# MAIN_AV_Final.net
KiCad netlist of a schematic drawn in EAGLE
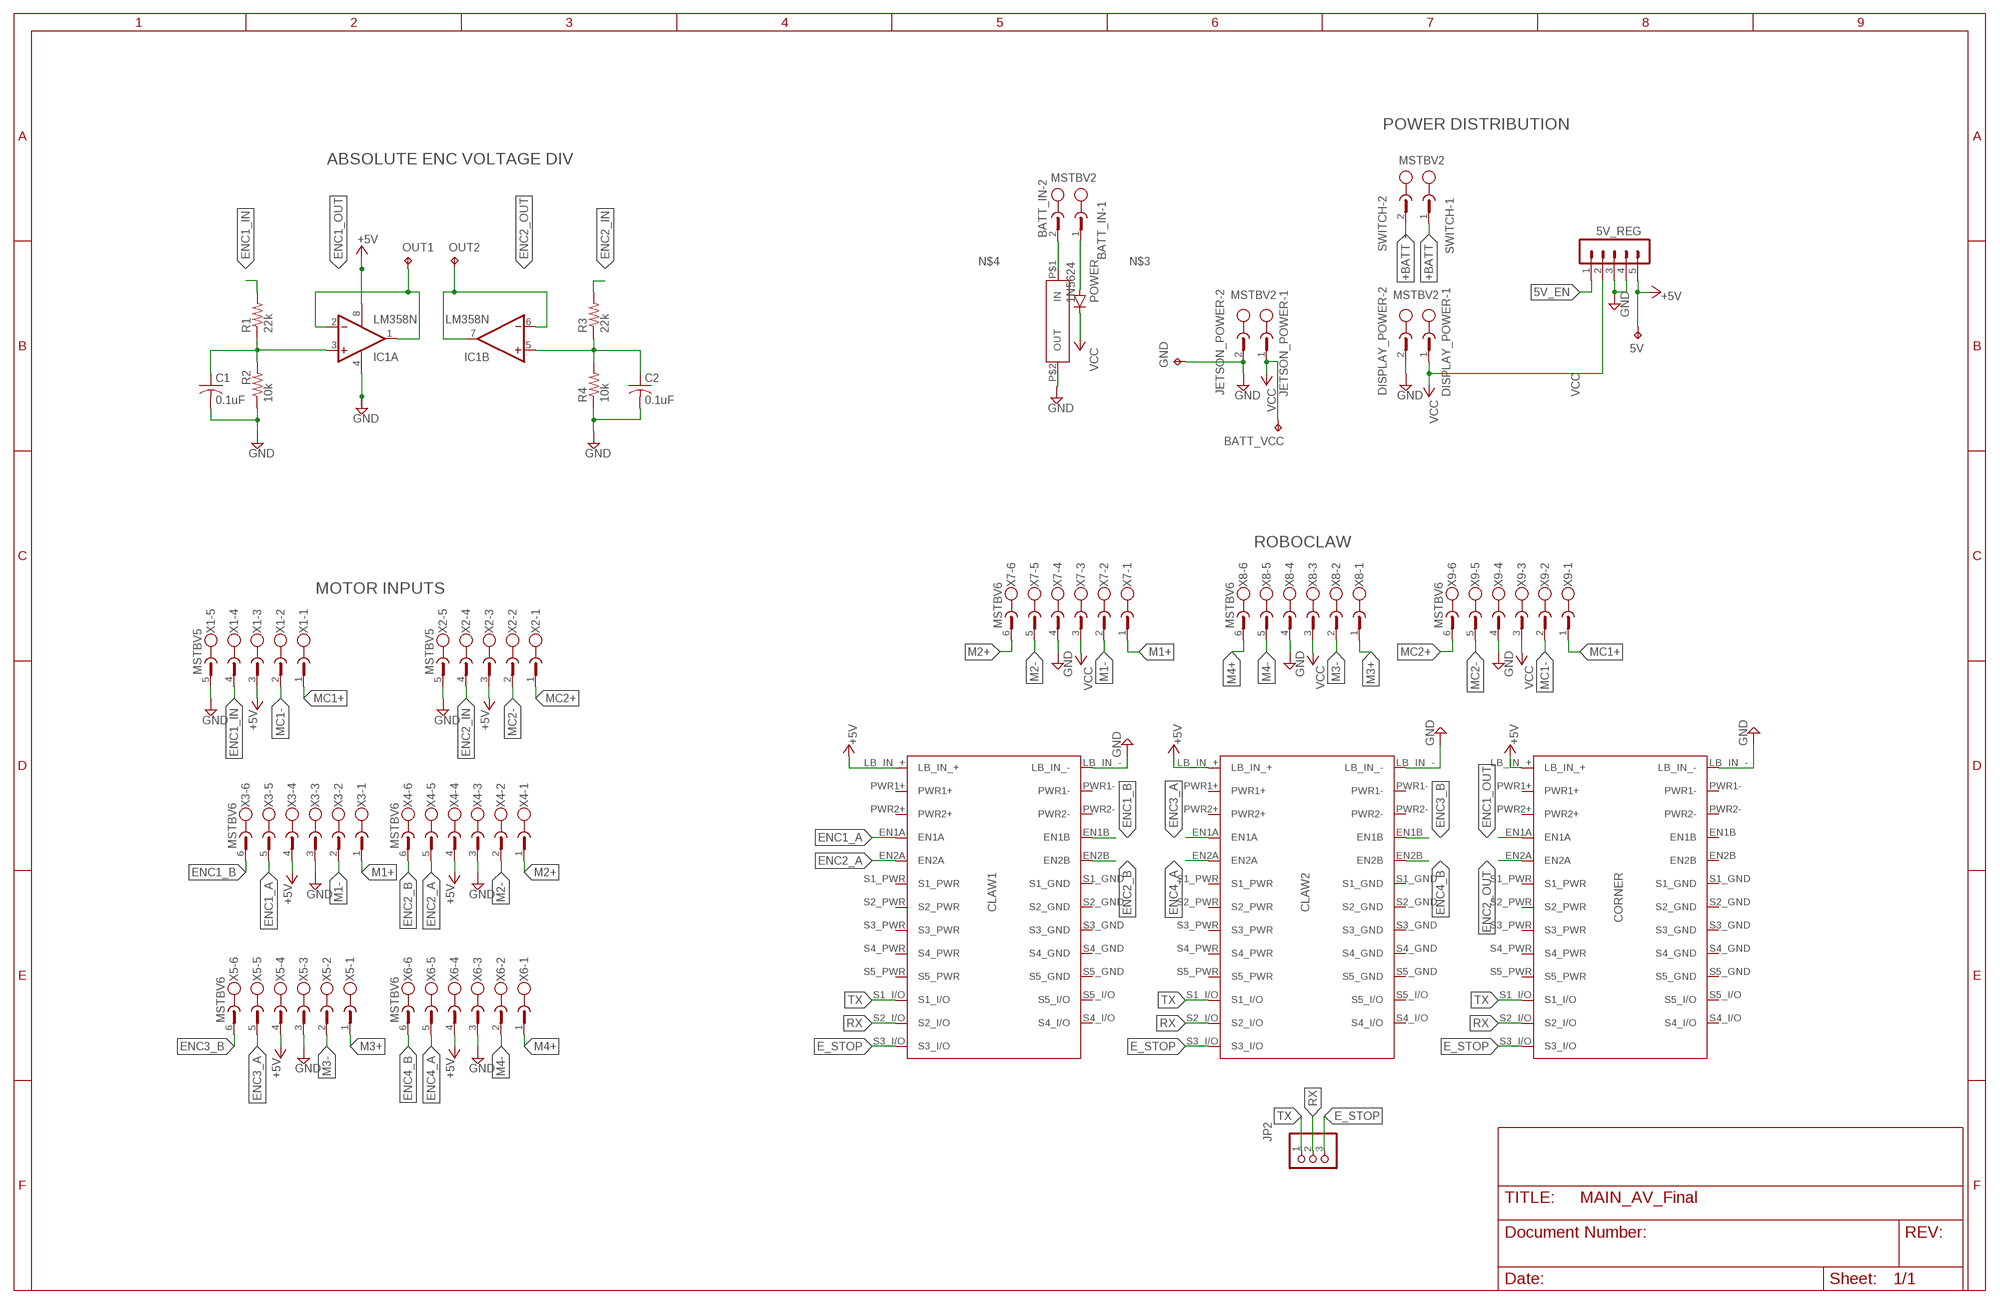
[diagram p0: schematic, sheet 1]

(export (version "E")
  (design (tool "Eeschema 10.0.6"))
  (components
    (comp (ref "5V")
      (value "TPTP10SQ")
      (footprint "eagle-import:TP10SQ")
      (libsource (lib "eagle-import") (part "TPTP10SQ"))
    )
    (comp (ref "5V_REG")
      (value "MA05-1")
      (footprint "eagle-import:MA05-1")
      (libsource (lib "eagle-import") (part "MA05-1"))
    )
    (comp (ref "BATT_IN")
      (value "MSTBV2")
      (footprint "eagle-import:MSTBV2")
      (fields (field (name "MPN") "MSTBV 2,5/2-GF-5.08"))
      (libsource (lib "eagle-import") (part "MSTBV2"))
    )
    (comp (ref "BATT_VCC")
      (value "TPTP10SQ")
      (footprint "eagle-import:TP10SQ")
      (libsource (lib "eagle-import") (part "TPTP10SQ"))
    )
    (comp (ref "C1")
      (value "0.1uF")
      (footprint "eagle-import:C050-024X044")
      (libsource (lib "eagle-import") (part "C-US050-024X044"))
    )
    (comp (ref "C2")
      (value "0.1uF")
      (footprint "eagle-import:C050-024X044")
      (libsource (lib "eagle-import") (part "C-US050-024X044"))
    )
    (comp (ref "CLAW1")
      (value "ROBOCLAW2X7A")
      (footprint "eagle-import:ROBOCLAW")
      (libsource (lib "eagle-import") (part "ROBOCLAW2X7A"))
    )
    (comp (ref "CLAW2")
      (value "ROBOCLAW2X7A")
      (footprint "eagle-import:ROBOCLAW")
      (libsource (lib "eagle-import") (part "ROBOCLAW2X7A"))
    )
    (comp (ref "CORNER")
      (value "ROBOCLAW2X7A")
      (footprint "eagle-import:ROBOCLAW")
      (libsource (lib "eagle-import") (part "ROBOCLAW2X7A"))
    )
    (comp (ref "DISPLAY_POWER")
      (value "MSTBV2")
      (footprint "eagle-import:MSTBV2")
      (fields (field (name "MPN") "MSTBV 2,5/2-GF-5.08"))
      (libsource (lib "eagle-import") (part "MSTBV2"))
    )
    (comp (ref "GND")
      (value "TPTP10SQ")
      (footprint "eagle-import:TP10SQ")
      (libsource (lib "eagle-import") (part "TPTP10SQ"))
    )
    (comp (ref "IC1")
      (value "LM358N")
      (footprint "eagle-import:DIL08")
      (libsource (lib "eagle-import") (part "LM358N"))
    )
    (comp (ref "JETSON_POWER")
      (value "MSTBV2")
      (footprint "eagle-import:MSTBV2")
      (fields (field (name "MPN") "MSTBV 2,5/2-GF-5.08"))
      (libsource (lib "eagle-import") (part "MSTBV2"))
    )
    (comp (ref "JP2")
      (value "PINHD-1X3")
      (footprint "eagle-import:1X03")
      (libsource (lib "eagle-import") (part "PINHD-1X3"))
    )
    (comp (ref "OUT1")
      (value "TPTP10SQ")
      (footprint "eagle-import:TP10SQ")
      (libsource (lib "eagle-import") (part "TPTP10SQ"))
    )
    (comp (ref "OUT2")
      (value "TPTP10SQ")
      (footprint "eagle-import:TP10SQ")
      (libsource (lib "eagle-import") (part "TPTP10SQ"))
    )
    (comp (ref "POWER")
      (value "1N5624")
      (footprint "eagle-import:DO201-15")
      (libsource (lib "eagle-import") (part "1N5624"))
    )
    (comp (ref "R1")
      (value "22k")
      (footprint "eagle-import:0204_7")
      (libsource (lib "eagle-import") (part "R-US_0204/7"))
    )
    (comp (ref "R2")
      (value "10k")
      (footprint "eagle-import:0204_7")
      (libsource (lib "eagle-import") (part "R-US_0204/7"))
    )
    (comp (ref "R3")
      (value "22k")
      (footprint "eagle-import:0204_7")
      (libsource (lib "eagle-import") (part "R-US_0204/7"))
    )
    (comp (ref "R4")
      (value "10k")
      (footprint "eagle-import:0204_7")
      (libsource (lib "eagle-import") (part "R-US_0204/7"))
    )
    (comp (ref "SWITCH")
      (value "MSTBV2")
      (footprint "eagle-import:MSTBV2")
      (fields (field (name "MPN") "MSTBV 2,5/2-GF-5.08"))
      (libsource (lib "eagle-import") (part "MSTBV2"))
    )
    (comp (ref "U$1")
      (value "FUSEHOLDER")
      (footprint "eagle-import:FUSEHOLDER")
      (libsource (lib "eagle-import") (part "FUSEHOLDER"))
    )
    (comp (ref "X1")
      (value "MSTBV5")
      (footprint "eagle-import:MSTBV5")
      (fields (field (name "MPN") "MSTBV 2,5/5-GF-5.08"))
      (libsource (lib "eagle-import") (part "MSTBV5"))
    )
    (comp (ref "X2")
      (value "MSTBV5")
      (footprint "eagle-import:MSTBV5")
      (fields (field (name "MPN") "MSTBV 2,5/5-GF-5.08"))
      (libsource (lib "eagle-import") (part "MSTBV5"))
    )
    (comp (ref "X3")
      (value "MSTBV6")
      (footprint "eagle-import:MSTBV6")
      (fields (field (name "MPN") "MSTBV 2,5/6-GF-5.08"))
      (libsource (lib "eagle-import") (part "MSTBV6"))
    )
    (comp (ref "X4")
      (value "MSTBV6")
      (footprint "eagle-import:MSTBV6")
      (fields (field (name "MPN") "MSTBV 2,5/6-GF-5.08"))
      (libsource (lib "eagle-import") (part "MSTBV6"))
    )
    (comp (ref "X5")
      (value "MSTBV6")
      (footprint "eagle-import:MSTBV6")
      (fields (field (name "MPN") "MSTBV 2,5/6-GF-5.08"))
      (libsource (lib "eagle-import") (part "MSTBV6"))
    )
    (comp (ref "X6")
      (value "MSTBV6")
      (footprint "eagle-import:MSTBV6")
      (fields (field (name "MPN") "MSTBV 2,5/6-GF-5.08"))
      (libsource (lib "eagle-import") (part "MSTBV6"))
    )
    (comp (ref "X7")
      (value "MSTBV6")
      (footprint "eagle-import:MSTBV6")
      (fields (field (name "MPN") "MSTBV 2,5/6-GF-5.08"))
      (libsource (lib "eagle-import") (part "MSTBV6"))
    )
    (comp (ref "X8")
      (value "MSTBV6")
      (footprint "eagle-import:MSTBV6")
      (fields (field (name "MPN") "MSTBV 2,5/6-GF-5.08"))
      (libsource (lib "eagle-import") (part "MSTBV6"))
    )
    (comp (ref "X9")
      (value "MSTBV6")
      (footprint "eagle-import:MSTBV6")
      (fields (field (name "MPN") "MSTBV 2,5/6-GF-5.08"))
      (libsource (lib "eagle-import") (part "MSTBV6"))
    )
  )
  (nets
    (net (code "1") (name "+5V") (class "Default")
      (node (ref "5V") (pin "TP") (pinfunction "TP_TP") (pintype "input"))
      (node (ref "5V_REG") (pin "5") (pinfunction "5_5") (pintype "passive"))
      (node (ref "CLAW1") (pin "LB_IN_+") (pinfunction "LB_IN_+_LB_IN_+") (pintype "bidirectional"))
      (node (ref "CLAW2") (pin "LB_IN_+") (pinfunction "LB_IN_+_LB_IN_+") (pintype "bidirectional"))
      (node (ref "CORNER") (pin "LB_IN_+") (pinfunction "LB_IN_+_LB_IN_+") (pintype "bidirectional"))
      (node (ref "IC1") (pin "8") (pinfunction "V+_8") (pintype "power_in"))
      (node (ref "X1") (pin "3") (pinfunction "1_3") (pintype "passive"))
      (node (ref "X2") (pin "3") (pinfunction "1_3") (pintype "passive"))
      (node (ref "X3") (pin "4") (pinfunction "1_4") (pintype "passive"))
      (node (ref "X4") (pin "4") (pinfunction "1_4") (pintype "passive"))
      (node (ref "X5") (pin "4") (pinfunction "1_4") (pintype "passive"))
      (node (ref "X6") (pin "4") (pinfunction "1_4") (pintype "passive"))
    )
    (net (code "2") (name "+BATT") (class "Default")
      (node (ref "SWITCH") (pin "1") (pinfunction "1_1") (pintype "passive"))
      (node (ref "SWITCH") (pin "2") (pinfunction "1_2") (pintype "passive"))
    )
    (net (code "3") (name "/N$3") (class "Default")
      (node (ref "BATT_IN") (pin "1") (pinfunction "1_1") (pintype "passive"))
      (node (ref "POWER") (pin "A") (pinfunction "A_A") (pintype "passive"))
    )
    (net (code "4") (name "/N$4") (class "Default")
      (node (ref "BATT_IN") (pin "2") (pinfunction "1_2") (pintype "passive"))
      (node (ref "U$1") (pin "P$1") (pinfunction "IN_P$1") (pintype "bidirectional"))
    )
    (net (code "5") (name "5V_EN") (class "Default")
      (node (ref "5V_REG") (pin "1") (pinfunction "1_1") (pintype "passive"))
    )
    (net (code "6") (name "ENC1_A") (class "Default")
      (node (ref "CLAW1") (pin "EN1A") (pinfunction "EN1A_EN1A") (pintype "bidirectional"))
      (node (ref "X3") (pin "5") (pinfunction "1_5") (pintype "passive"))
    )
    (net (code "7") (name "ENC1_B") (class "Default")
      (node (ref "CLAW1") (pin "EN1B") (pinfunction "EN1B_EN1B") (pintype "bidirectional"))
      (node (ref "X3") (pin "6") (pinfunction "1_6") (pintype "passive"))
    )
    (net (code "8") (name "ENC1_IN") (class "Default")
      (node (ref "R1") (pin "2") (pinfunction "2_2") (pintype "passive"))
      (node (ref "X1") (pin "4") (pinfunction "1_4") (pintype "passive"))
    )
    (net (code "9") (name "ENC1_OUT") (class "Default")
      (node (ref "CORNER") (pin "EN1A") (pinfunction "EN1A_EN1A") (pintype "bidirectional"))
      (node (ref "IC1") (pin "1") (pinfunction "OUT_1") (pintype "output"))
      (node (ref "IC1") (pin "2") (pinfunction "-IN_2") (pintype "input"))
      (node (ref "OUT1") (pin "TP") (pinfunction "TP_TP") (pintype "input"))
    )
    (net (code "10") (name "ENC2_A") (class "Default")
      (node (ref "CLAW1") (pin "EN2A") (pinfunction "EN2A_EN2A") (pintype "bidirectional"))
      (node (ref "X4") (pin "5") (pinfunction "1_5") (pintype "passive"))
    )
    (net (code "11") (name "ENC2_B") (class "Default")
      (node (ref "CLAW1") (pin "EN2B") (pinfunction "EN2B_EN2B") (pintype "bidirectional"))
      (node (ref "X4") (pin "6") (pinfunction "1_6") (pintype "passive"))
    )
    (net (code "12") (name "ENC2_IN") (class "Default")
      (node (ref "R3") (pin "2") (pinfunction "2_2") (pintype "passive"))
      (node (ref "X2") (pin "4") (pinfunction "1_4") (pintype "passive"))
    )
    (net (code "13") (name "ENC2_OUT") (class "Default")
      (node (ref "CORNER") (pin "EN2A") (pinfunction "EN2A_EN2A") (pintype "bidirectional"))
      (node (ref "IC1") (pin "6") (pinfunction "-IN_6") (pintype "input"))
      (node (ref "IC1") (pin "7") (pinfunction "OUT_7") (pintype "output"))
      (node (ref "OUT2") (pin "TP") (pinfunction "TP_TP") (pintype "input"))
    )
    (net (code "14") (name "ENC3_A") (class "Default")
      (node (ref "CLAW2") (pin "EN1A") (pinfunction "EN1A_EN1A") (pintype "bidirectional"))
      (node (ref "X5") (pin "5") (pinfunction "1_5") (pintype "passive"))
    )
    (net (code "15") (name "ENC3_B") (class "Default")
      (node (ref "CLAW2") (pin "EN1B") (pinfunction "EN1B_EN1B") (pintype "bidirectional"))
      (node (ref "X5") (pin "6") (pinfunction "1_6") (pintype "passive"))
    )
    (net (code "16") (name "ENC4_A") (class "Default")
      (node (ref "CLAW2") (pin "EN2A") (pinfunction "EN2A_EN2A") (pintype "bidirectional"))
      (node (ref "X6") (pin "5") (pinfunction "1_5") (pintype "passive"))
    )
    (net (code "17") (name "ENC4_B") (class "Default")
      (node (ref "CLAW2") (pin "EN2B") (pinfunction "EN2B_EN2B") (pintype "bidirectional"))
      (node (ref "X6") (pin "6") (pinfunction "1_6") (pintype "passive"))
    )
    (net (code "18") (name "E_STOP") (class "Default")
      (node (ref "CLAW1") (pin "S3_I/O") (pinfunction "S3_I/O_S3_I/O") (pintype "bidirectional"))
      (node (ref "CLAW2") (pin "S3_I/O") (pinfunction "S3_I/O_S3_I/O") (pintype "bidirectional"))
      (node (ref "CORNER") (pin "S3_I/O") (pinfunction "S3_I/O_S3_I/O") (pintype "bidirectional"))
      (node (ref "JP2") (pin "3") (pinfunction "3_3") (pintype "passive"))
    )
    (net (code "19") (name "GND") (class "Default")
      (node (ref "5V_REG") (pin "3") (pinfunction "3_3") (pintype "passive"))
      (node (ref "5V_REG") (pin "4") (pinfunction "4_4") (pintype "passive"))
      (node (ref "C1") (pin "2") (pinfunction "2_2") (pintype "passive"))
      (node (ref "C2") (pin "2") (pinfunction "2_2") (pintype "passive"))
      (node (ref "CLAW1") (pin "LB_IN_-") (pinfunction "LB_IN_-_LB_IN_-") (pintype "bidirectional"))
      (node (ref "CLAW2") (pin "LB_IN_-") (pinfunction "LB_IN_-_LB_IN_-") (pintype "bidirectional"))
      (node (ref "CORNER") (pin "LB_IN_-") (pinfunction "LB_IN_-_LB_IN_-") (pintype "bidirectional"))
      (node (ref "DISPLAY_POWER") (pin "2") (pinfunction "1_2") (pintype "passive"))
      (node (ref "GND") (pin "TP") (pinfunction "TP_TP") (pintype "input"))
      (node (ref "IC1") (pin "4") (pinfunction "V-_4") (pintype "power_in"))
      (node (ref "JETSON_POWER") (pin "2") (pinfunction "1_2") (pintype "passive"))
      (node (ref "R2") (pin "1") (pinfunction "1_1") (pintype "passive"))
      (node (ref "R4") (pin "1") (pinfunction "1_1") (pintype "passive"))
      (node (ref "U$1") (pin "P$2") (pinfunction "OUT_P$2") (pintype "bidirectional"))
      (node (ref "X1") (pin "5") (pinfunction "1_5") (pintype "passive"))
      (node (ref "X2") (pin "5") (pinfunction "1_5") (pintype "passive"))
      (node (ref "X3") (pin "3") (pinfunction "1_3") (pintype "passive"))
      (node (ref "X4") (pin "3") (pinfunction "1_3") (pintype "passive"))
      (node (ref "X5") (pin "3") (pinfunction "1_3") (pintype "passive"))
      (node (ref "X6") (pin "3") (pinfunction "1_3") (pintype "passive"))
      (node (ref "X7") (pin "4") (pinfunction "1_4") (pintype "passive"))
      (node (ref "X8") (pin "4") (pinfunction "1_4") (pintype "passive"))
      (node (ref "X9") (pin "4") (pinfunction "1_4") (pintype "passive"))
    )
    (net (code "20") (name "M1+") (class "Default")
      (node (ref "X3") (pin "1") (pinfunction "1_1") (pintype "passive"))
      (node (ref "X7") (pin "1") (pinfunction "1_1") (pintype "passive"))
    )
    (net (code "21") (name "M1-") (class "Default")
      (node (ref "X3") (pin "2") (pinfunction "1_2") (pintype "passive"))
      (node (ref "X7") (pin "2") (pinfunction "1_2") (pintype "passive"))
    )
    (net (code "22") (name "M2+") (class "Default")
      (node (ref "X4") (pin "1") (pinfunction "1_1") (pintype "passive"))
      (node (ref "X7") (pin "6") (pinfunction "1_6") (pintype "passive"))
    )
    (net (code "23") (name "M2-") (class "Default")
      (node (ref "X4") (pin "2") (pinfunction "1_2") (pintype "passive"))
      (node (ref "X7") (pin "5") (pinfunction "1_5") (pintype "passive"))
    )
    (net (code "24") (name "M3+") (class "Default")
      (node (ref "X5") (pin "1") (pinfunction "1_1") (pintype "passive"))
      (node (ref "X8") (pin "1") (pinfunction "1_1") (pintype "passive"))
    )
    (net (code "25") (name "M3-") (class "Default")
      (node (ref "X5") (pin "2") (pinfunction "1_2") (pintype "passive"))
      (node (ref "X8") (pin "2") (pinfunction "1_2") (pintype "passive"))
    )
    (net (code "26") (name "M4+") (class "Default")
      (node (ref "X6") (pin "1") (pinfunction "1_1") (pintype "passive"))
      (node (ref "X8") (pin "6") (pinfunction "1_6") (pintype "passive"))
    )
    (net (code "27") (name "M4-") (class "Default")
      (node (ref "X6") (pin "2") (pinfunction "1_2") (pintype "passive"))
      (node (ref "X8") (pin "5") (pinfunction "1_5") (pintype "passive"))
    )
    (net (code "28") (name "MC1+") (class "Default")
      (node (ref "X1") (pin "1") (pinfunction "1_1") (pintype "passive"))
      (node (ref "X9") (pin "1") (pinfunction "1_1") (pintype "passive"))
    )
    (net (code "29") (name "MC1-") (class "Default")
      (node (ref "X1") (pin "2") (pinfunction "1_2") (pintype "passive"))
      (node (ref "X9") (pin "2") (pinfunction "1_2") (pintype "passive"))
    )
    (net (code "30") (name "MC2+") (class "Default")
      (node (ref "X2") (pin "1") (pinfunction "1_1") (pintype "passive"))
      (node (ref "X9") (pin "6") (pinfunction "1_6") (pintype "passive"))
    )
    (net (code "31") (name "MC2-") (class "Default")
      (node (ref "X2") (pin "2") (pinfunction "1_2") (pintype "passive"))
      (node (ref "X9") (pin "5") (pinfunction "1_5") (pintype "passive"))
    )
    (net (code "32") (name "Net-(IC1A-+IN)") (class "Default")
      (node (ref "C1") (pin "1") (pinfunction "1_1") (pintype "passive"))
      (node (ref "IC1") (pin "3") (pinfunction "+IN_3") (pintype "input"))
      (node (ref "R1") (pin "1") (pinfunction "1_1") (pintype "passive"))
      (node (ref "R2") (pin "2") (pinfunction "2_2") (pintype "passive"))
    )
    (net (code "33") (name "Net-(IC1B-+IN)") (class "Default")
      (node (ref "C2") (pin "1") (pinfunction "1_1") (pintype "passive"))
      (node (ref "IC1") (pin "5") (pinfunction "+IN_5") (pintype "input"))
      (node (ref "R3") (pin "1") (pinfunction "1_1") (pintype "passive"))
      (node (ref "R4") (pin "2") (pinfunction "2_2") (pintype "passive"))
    )
    (net (code "34") (name "RX") (class "Default")
      (node (ref "CLAW1") (pin "S2_I/O") (pinfunction "S2_I/O_S2_I/O") (pintype "bidirectional"))
      (node (ref "CLAW2") (pin "S2_I/O") (pinfunction "S2_I/O_S2_I/O") (pintype "bidirectional"))
      (node (ref "CORNER") (pin "S2_I/O") (pinfunction "S2_I/O_S2_I/O") (pintype "bidirectional"))
      (node (ref "JP2") (pin "2") (pinfunction "2_2") (pintype "passive"))
    )
    (net (code "35") (name "TX") (class "Default")
      (node (ref "CLAW1") (pin "S1_I/O") (pinfunction "S1_I/O_S1_I/O") (pintype "bidirectional"))
      (node (ref "CLAW2") (pin "S1_I/O") (pinfunction "S1_I/O_S1_I/O") (pintype "bidirectional"))
      (node (ref "CORNER") (pin "S1_I/O") (pinfunction "S1_I/O_S1_I/O") (pintype "bidirectional"))
      (node (ref "JP2") (pin "1") (pinfunction "1_1") (pintype "passive"))
    )
    (net (code "36") (name "VCC") (class "Default")
      (node (ref "5V_REG") (pin "2") (pinfunction "2_2") (pintype "passive"))
      (node (ref "BATT_VCC") (pin "TP") (pinfunction "TP_TP") (pintype "input"))
      (node (ref "DISPLAY_POWER") (pin "1") (pinfunction "1_1") (pintype "passive"))
      (node (ref "JETSON_POWER") (pin "1") (pinfunction "1_1") (pintype "passive"))
      (node (ref "POWER") (pin "C") (pinfunction "C_C") (pintype "passive"))
      (node (ref "X7") (pin "3") (pinfunction "1_3") (pintype "passive"))
      (node (ref "X8") (pin "3") (pinfunction "1_3") (pintype "passive"))
      (node (ref "X9") (pin "3") (pinfunction "1_3") (pintype "passive"))
    )
    (net (code "37") (name "unconnected-(CLAW1-PadPWR1+)") (class "Default")
      (node (ref "CLAW1") (pin "PWR1+") (pinfunction "PWR1+_PWR1+") (pintype "bidirectional"))
    )
    (net (code "38") (name "unconnected-(CLAW1-PadPWR1-)") (class "Default")
      (node (ref "CLAW1") (pin "PWR1-") (pinfunction "PWR1-_PWR1-") (pintype "bidirectional"))
    )
    (net (code "39") (name "unconnected-(CLAW1-PadPWR2+)") (class "Default")
      (node (ref "CLAW1") (pin "PWR2+") (pinfunction "PWR2+_PWR2+") (pintype "bidirectional"))
    )
    (net (code "40") (name "unconnected-(CLAW1-PadPWR2-)") (class "Default")
      (node (ref "CLAW1") (pin "PWR2-") (pinfunction "PWR2-_PWR2-") (pintype "bidirectional"))
    )
    (net (code "41") (name "unconnected-(CLAW1-PadS1_GND)") (class "Default")
      (node (ref "CLAW1") (pin "S1_GND") (pinfunction "S1_GND_S1_GND") (pintype "bidirectional"))
    )
    (net (code "42") (name "unconnected-(CLAW1-PadS1_PWR)") (class "Default")
      (node (ref "CLAW1") (pin "S1_PWR") (pinfunction "S1_PWR_S1_PWR") (pintype "bidirectional"))
    )
    (net (code "43") (name "unconnected-(CLAW1-PadS2_GND)") (class "Default")
      (node (ref "CLAW1") (pin "S2_GND") (pinfunction "S2_GND_S2_GND") (pintype "bidirectional"))
    )
    (net (code "44") (name "unconnected-(CLAW1-PadS2_PWR)") (class "Default")
      (node (ref "CLAW1") (pin "S2_PWR") (pinfunction "S2_PWR_S2_PWR") (pintype "bidirectional"))
    )
    (net (code "45") (name "unconnected-(CLAW1-PadS3_GND)") (class "Default")
      (node (ref "CLAW1") (pin "S3_GND") (pinfunction "S3_GND_S3_GND") (pintype "bidirectional"))
    )
    (net (code "46") (name "unconnected-(CLAW1-PadS3_PWR)") (class "Default")
      (node (ref "CLAW1") (pin "S3_PWR") (pinfunction "S3_PWR_S3_PWR") (pintype "bidirectional"))
    )
    (net (code "47") (name "unconnected-(CLAW1-PadS4_GND)") (class "Default")
      (node (ref "CLAW1") (pin "S4_GND") (pinfunction "S4_GND_S4_GND") (pintype "bidirectional"))
    )
    (net (code "48") (name "unconnected-(CLAW1-PadS4_I{slash}O)") (class "Default")
      (node (ref "CLAW1") (pin "S4_I/O") (pinfunction "S4_I/O_S4_I/O") (pintype "bidirectional"))
    )
    (net (code "49") (name "unconnected-(CLAW1-PadS4_PWR)") (class "Default")
      (node (ref "CLAW1") (pin "S4_PWR") (pinfunction "S4_PWR_S4_PWR") (pintype "bidirectional"))
    )
    (net (code "50") (name "unconnected-(CLAW1-PadS5_GND)") (class "Default")
      (node (ref "CLAW1") (pin "S5_GND") (pinfunction "S5_GND_S5_GND") (pintype "bidirectional"))
    )
    (net (code "51") (name "unconnected-(CLAW1-PadS5_I{slash}O)") (class "Default")
      (node (ref "CLAW1") (pin "S5_I/O") (pinfunction "S5_I/O_S5_I/O") (pintype "bidirectional"))
    )
    (net (code "52") (name "unconnected-(CLAW1-PadS5_PWR)") (class "Default")
      (node (ref "CLAW1") (pin "S5_PWR") (pinfunction "S5_PWR_S5_PWR") (pintype "bidirectional"))
    )
    (net (code "53") (name "unconnected-(CLAW2-PadPWR1+)") (class "Default")
      (node (ref "CLAW2") (pin "PWR1+") (pinfunction "PWR1+_PWR1+") (pintype "bidirectional"))
    )
    (net (code "54") (name "unconnected-(CLAW2-PadPWR1-)") (class "Default")
      (node (ref "CLAW2") (pin "PWR1-") (pinfunction "PWR1-_PWR1-") (pintype "bidirectional"))
    )
    (net (code "55") (name "unconnected-(CLAW2-PadPWR2+)") (class "Default")
      (node (ref "CLAW2") (pin "PWR2+") (pinfunction "PWR2+_PWR2+") (pintype "bidirectional"))
    )
    (net (code "56") (name "unconnected-(CLAW2-PadPWR2-)") (class "Default")
      (node (ref "CLAW2") (pin "PWR2-") (pinfunction "PWR2-_PWR2-") (pintype "bidirectional"))
    )
    (net (code "57") (name "unconnected-(CLAW2-PadS1_GND)") (class "Default")
      (node (ref "CLAW2") (pin "S1_GND") (pinfunction "S1_GND_S1_GND") (pintype "bidirectional"))
    )
    (net (code "58") (name "unconnected-(CLAW2-PadS1_PWR)") (class "Default")
      (node (ref "CLAW2") (pin "S1_PWR") (pinfunction "S1_PWR_S1_PWR") (pintype "bidirectional"))
    )
    (net (code "59") (name "unconnected-(CLAW2-PadS2_GND)") (class "Default")
      (node (ref "CLAW2") (pin "S2_GND") (pinfunction "S2_GND_S2_GND") (pintype "bidirectional"))
    )
    (net (code "60") (name "unconnected-(CLAW2-PadS2_PWR)") (class "Default")
      (node (ref "CLAW2") (pin "S2_PWR") (pinfunction "S2_PWR_S2_PWR") (pintype "bidirectional"))
    )
    (net (code "61") (name "unconnected-(CLAW2-PadS3_GND)") (class "Default")
      (node (ref "CLAW2") (pin "S3_GND") (pinfunction "S3_GND_S3_GND") (pintype "bidirectional"))
    )
    (net (code "62") (name "unconnected-(CLAW2-PadS3_PWR)") (class "Default")
      (node (ref "CLAW2") (pin "S3_PWR") (pinfunction "S3_PWR_S3_PWR") (pintype "bidirectional"))
    )
    (net (code "63") (name "unconnected-(CLAW2-PadS4_GND)") (class "Default")
      (node (ref "CLAW2") (pin "S4_GND") (pinfunction "S4_GND_S4_GND") (pintype "bidirectional"))
    )
    (net (code "64") (name "unconnected-(CLAW2-PadS4_I{slash}O)") (class "Default")
      (node (ref "CLAW2") (pin "S4_I/O") (pinfunction "S4_I/O_S4_I/O") (pintype "bidirectional"))
    )
    (net (code "65") (name "unconnected-(CLAW2-PadS4_PWR)") (class "Default")
      (node (ref "CLAW2") (pin "S4_PWR") (pinfunction "S4_PWR_S4_PWR") (pintype "bidirectional"))
    )
    (net (code "66") (name "unconnected-(CLAW2-PadS5_GND)") (class "Default")
      (node (ref "CLAW2") (pin "S5_GND") (pinfunction "S5_GND_S5_GND") (pintype "bidirectional"))
    )
    (net (code "67") (name "unconnected-(CLAW2-PadS5_I{slash}O)") (class "Default")
      (node (ref "CLAW2") (pin "S5_I/O") (pinfunction "S5_I/O_S5_I/O") (pintype "bidirectional"))
    )
    (net (code "68") (name "unconnected-(CLAW2-PadS5_PWR)") (class "Default")
      (node (ref "CLAW2") (pin "S5_PWR") (pinfunction "S5_PWR_S5_PWR") (pintype "bidirectional"))
    )
    (net (code "69") (name "unconnected-(CORNER-PadEN1B)") (class "Default")
      (node (ref "CORNER") (pin "EN1B") (pinfunction "EN1B_EN1B") (pintype "bidirectional"))
    )
    (net (code "70") (name "unconnected-(CORNER-PadEN2B)") (class "Default")
      (node (ref "CORNER") (pin "EN2B") (pinfunction "EN2B_EN2B") (pintype "bidirectional"))
    )
    (net (code "71") (name "unconnected-(CORNER-PadPWR1+)") (class "Default")
      (node (ref "CORNER") (pin "PWR1+") (pinfunction "PWR1+_PWR1+") (pintype "bidirectional"))
    )
    (net (code "72") (name "unconnected-(CORNER-PadPWR1-)") (class "Default")
      (node (ref "CORNER") (pin "PWR1-") (pinfunction "PWR1-_PWR1-") (pintype "bidirectional"))
    )
    (net (code "73") (name "unconnected-(CORNER-PadPWR2+)") (class "Default")
      (node (ref "CORNER") (pin "PWR2+") (pinfunction "PWR2+_PWR2+") (pintype "bidirectional"))
    )
    (net (code "74") (name "unconnected-(CORNER-PadPWR2-)") (class "Default")
      (node (ref "CORNER") (pin "PWR2-") (pinfunction "PWR2-_PWR2-") (pintype "bidirectional"))
    )
    (net (code "75") (name "unconnected-(CORNER-PadS1_GND)") (class "Default")
      (node (ref "CORNER") (pin "S1_GND") (pinfunction "S1_GND_S1_GND") (pintype "bidirectional"))
    )
    (net (code "76") (name "unconnected-(CORNER-PadS1_PWR)") (class "Default")
      (node (ref "CORNER") (pin "S1_PWR") (pinfunction "S1_PWR_S1_PWR") (pintype "bidirectional"))
    )
    (net (code "77") (name "unconnected-(CORNER-PadS2_GND)") (class "Default")
      (node (ref "CORNER") (pin "S2_GND") (pinfunction "S2_GND_S2_GND") (pintype "bidirectional"))
    )
    (net (code "78") (name "unconnected-(CORNER-PadS2_PWR)") (class "Default")
      (node (ref "CORNER") (pin "S2_PWR") (pinfunction "S2_PWR_S2_PWR") (pintype "bidirectional"))
    )
    (net (code "79") (name "unconnected-(CORNER-PadS3_GND)") (class "Default")
      (node (ref "CORNER") (pin "S3_GND") (pinfunction "S3_GND_S3_GND") (pintype "bidirectional"))
    )
    (net (code "80") (name "unconnected-(CORNER-PadS3_PWR)") (class "Default")
      (node (ref "CORNER") (pin "S3_PWR") (pinfunction "S3_PWR_S3_PWR") (pintype "bidirectional"))
    )
    (net (code "81") (name "unconnected-(CORNER-PadS4_GND)") (class "Default")
      (node (ref "CORNER") (pin "S4_GND") (pinfunction "S4_GND_S4_GND") (pintype "bidirectional"))
    )
    (net (code "82") (name "unconnected-(CORNER-PadS4_I{slash}O)") (class "Default")
      (node (ref "CORNER") (pin "S4_I/O") (pinfunction "S4_I/O_S4_I/O") (pintype "bidirectional"))
    )
    (net (code "83") (name "unconnected-(CORNER-PadS4_PWR)") (class "Default")
      (node (ref "CORNER") (pin "S4_PWR") (pinfunction "S4_PWR_S4_PWR") (pintype "bidirectional"))
    )
    (net (code "84") (name "unconnected-(CORNER-PadS5_GND)") (class "Default")
      (node (ref "CORNER") (pin "S5_GND") (pinfunction "S5_GND_S5_GND") (pintype "bidirectional"))
    )
    (net (code "85") (name "unconnected-(CORNER-PadS5_I{slash}O)") (class "Default")
      (node (ref "CORNER") (pin "S5_I/O") (pinfunction "S5_I/O_S5_I/O") (pintype "bidirectional"))
    )
    (net (code "86") (name "unconnected-(CORNER-PadS5_PWR)") (class "Default")
      (node (ref "CORNER") (pin "S5_PWR") (pinfunction "S5_PWR_S5_PWR") (pintype "bidirectional"))
    )
  )
)
